# ConfigMultiplexer.net
KiCad netlist of a schematic drawn in Altium Designer
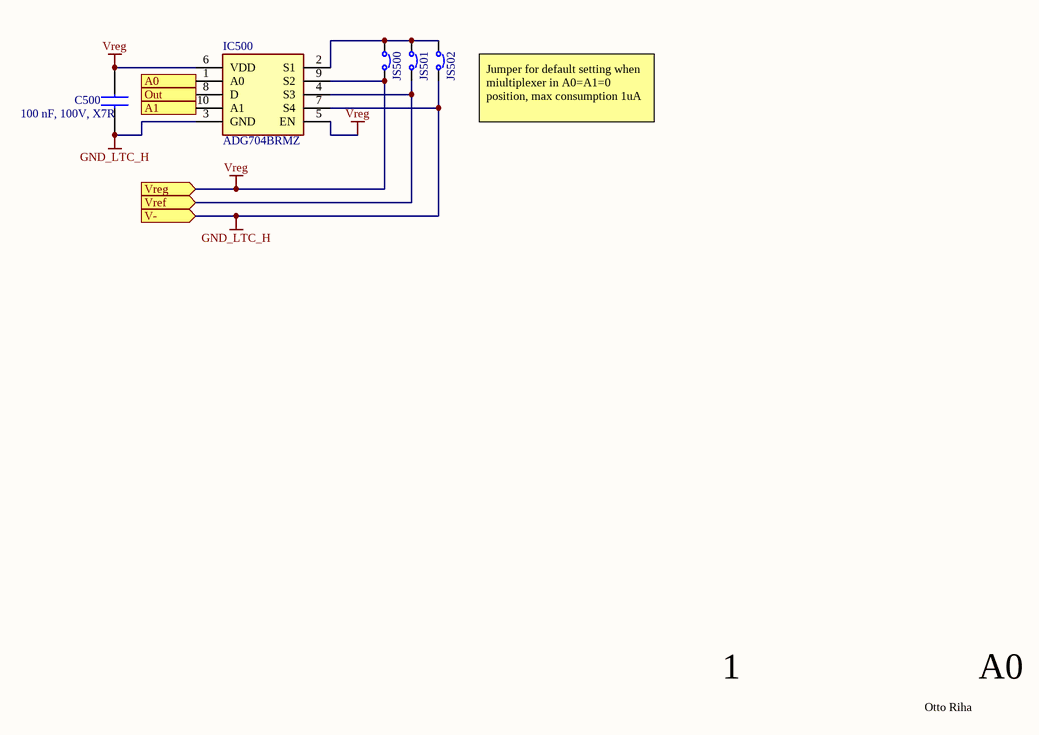
[diagram p0: ConfigMultiplexer.SchDoc]

(export (version "E")
  (design (tool "Eeschema 10.0.6"))
  (components
    (comp (ref "C500")
      (value "100 nF, 100V, X7R")
      (footprint "SamacSys:MAJx16")
      (description "Capacitor 100nF, 100V, X7R")
      (fields
        (field (name "MANUFACTURER_PART_NUMBER") "MAJCH168BB7104KTEA01")
        (field (name "MOUSER PART NUMBER") "963-MAJCH168BB7104KT")
      )
      (libsource (lib "SamacSys") (part "MAJCH168BB7104KTEA01"))
    )
    (comp (ref "IC500")
      (value "ADG704BRMZ")
      (footprint "SamacSys:SOP50P490X110-10N")
      (description "Integrated Circuit")
      (fields (field (name "MOUSER PART NUMBER") "584-ADG704BRMZ"))
      (libsource (lib "SamacSys") (part "ADG704BRMZ"))
    )
    (comp (ref "JS500")
      (value "SolderJumper")
      (footprint "SolderJumper")
      (libsource (lib "SamacSys") (part "SolderJumper"))
    )
    (comp (ref "JS501")
      (value "SolderJumper")
      (footprint "SolderJumper")
      (libsource (lib "SamacSys") (part "SolderJumper"))
    )
    (comp (ref "JS502")
      (value "SolderJumper")
      (footprint "SolderJumper")
      (libsource (lib "SamacSys") (part "SolderJumper"))
    )
  )
  (nets
    (net (code "1") (name "/A0") (class "Default")
      (node (ref "IC500") (pin "1") (pinfunction "A0_1") (pintype "passive"))
    )
    (net (code "2") (name "/A1") (class "Default")
      (node (ref "IC500") (pin "10") (pinfunction "A1_10") (pintype "passive"))
    )
    (net (code "3") (name "/Out") (class "Default")
      (node (ref "IC500") (pin "8") (pinfunction "D_8") (pintype "passive"))
    )
    (net (code "4") (name "/Vref") (class "Default")
      (node (ref "IC500") (pin "4") (pinfunction "S3_4") (pintype "passive"))
      (node (ref "JS501") (pin "1") (pinfunction "1_1") (pintype "passive"))
    )
    (net (code "5") (name "GND_LTC_H") (class "Default")
      (node (ref "C500") (pin "1") (pinfunction "1_1") (pintype "passive"))
      (node (ref "IC500") (pin "3") (pinfunction "GND_3") (pintype "passive"))
      (node (ref "IC500") (pin "7") (pinfunction "S4_7") (pintype "passive"))
      (node (ref "JS502") (pin "1") (pinfunction "1_1") (pintype "passive"))
    )
    (net (code "6") (name "Net-(IC500-S1)") (class "Default")
      (node (ref "IC500") (pin "2") (pinfunction "S1_2") (pintype "passive"))
      (node (ref "JS500") (pin "2") (pinfunction "2_2") (pintype "passive"))
      (node (ref "JS501") (pin "2") (pinfunction "2_2") (pintype "passive"))
      (node (ref "JS502") (pin "2") (pinfunction "2_2") (pintype "passive"))
    )
    (net (code "7") (name "Vreg") (class "Default")
      (node (ref "C500") (pin "2") (pinfunction "2_2") (pintype "passive"))
      (node (ref "IC500") (pin "5") (pinfunction "EN_5") (pintype "passive"))
      (node (ref "IC500") (pin "6") (pinfunction "VDD_6") (pintype "passive"))
      (node (ref "IC500") (pin "9") (pinfunction "S2_9") (pintype "passive"))
      (node (ref "JS500") (pin "1") (pinfunction "1_1") (pintype "passive"))
    )
  )
)
